# sd-card.net
KiCad netlist of a schematic drawn in Altium Designer
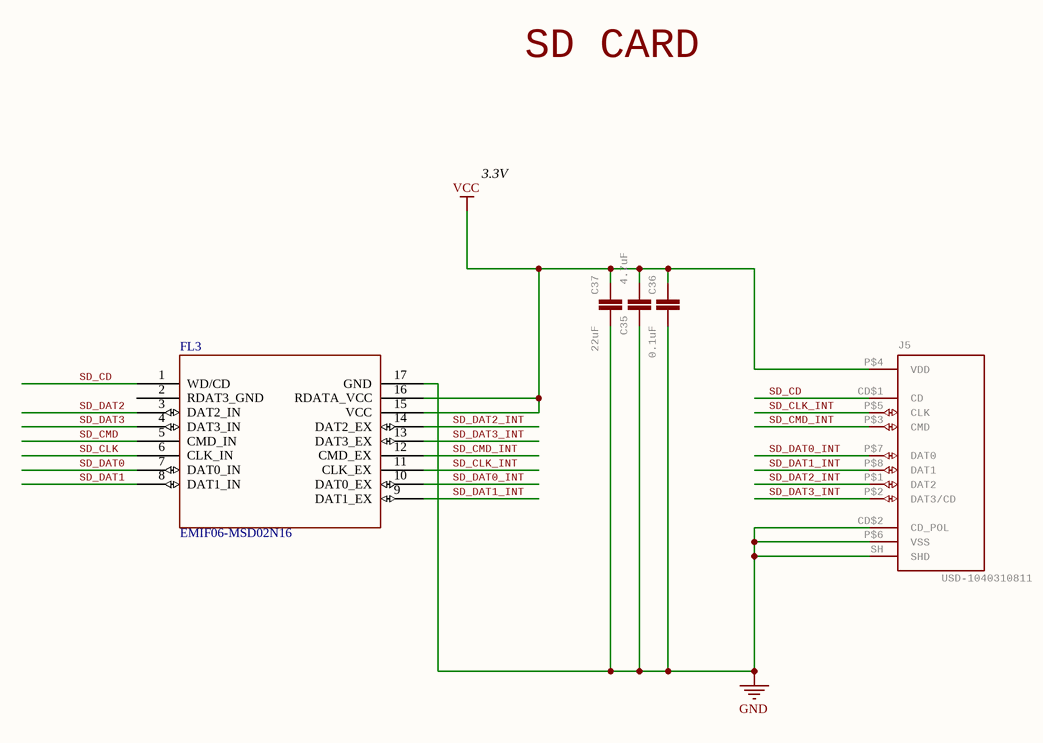
[diagram p0: sd-card.SchDoc]

(export (version "E")
  (design (tool "Eeschema 10.0.6"))
  (components
    (comp (ref "C35")
      (value "4.7uF")
      (footprint "0402-CAP")
      (description "CapacitorStandard 0603 ceramic capacitor, and 0.1\" leaded capacitor.")
      (fields (field (name "MPN") "JMK105BBJ475MV-F"))
      (libsource (lib "rt10") (part "CAP0402-CAP"))
    )
    (comp (ref "C36")
      (value "0.1uF")
      (footprint "0402-CAP")
      (description "CAPACITOR, European symbol")
      (fields (field (name "MPN") "C0402C104Z4VAC"))
      (libsource (lib "rt10") (part "C-EUC0201"))
    )
    (comp (ref "C37")
      (value "22uF")
      (footprint "0805")
      (fields (field (name "MPN") "CL21A226MQQNNNE"))
      (libsource (lib "rt10") (part "22UF-0805-6.3V-20%"))
    )
    (comp (ref "FL3")
      (value "EMIF06-MSD02N16")
      (footprint "MICROQFN16_1p25x3p55x0p4_STM")
      (description "No Description Available")
      (libsource (lib "rt10") (part "EMIF06-MSD02N16"))
    )
    (comp (ref "J5")
      (value "USD-1040310811")
      (footprint "1040310811")
      (description "uSD Slot")
      (fields (field (name "MPN") "104031-0811"))
      (libsource (lib "rt10") (part "USD-1040310811"))
    )
  )
  (nets
    (net (code "1") (name "/SD_CD") (class "Default")
      (node (ref "FL3") (pin "1") (pinfunction "WD/CD_1") (pintype "passive"))
      (node (ref "J5") (pin "CD$1") (pinfunction "CD_CD$1") (pintype "power_in"))
    )
    (net (code "2") (name "/SD_CLK") (class "Default")
      (node (ref "FL3") (pin "6") (pinfunction "CLK_IN_6") (pintype "passive"))
    )
    (net (code "3") (name "/SD_CLK_INT") (class "Default")
      (node (ref "FL3") (pin "11") (pinfunction "CLK_EX_11") (pintype "passive"))
      (node (ref "J5") (pin "P$5") (pinfunction "CLK_P$5") (pintype "bidirectional"))
    )
    (net (code "4") (name "/SD_CMD") (class "Default")
      (node (ref "FL3") (pin "5") (pinfunction "CMD_IN_5") (pintype "passive"))
    )
    (net (code "5") (name "/SD_CMD_INT") (class "Default")
      (node (ref "FL3") (pin "12") (pinfunction "CMD_EX_12") (pintype "passive"))
      (node (ref "J5") (pin "P$3") (pinfunction "CMD_P$3") (pintype "bidirectional"))
    )
    (net (code "6") (name "/SD_DAT0") (class "Default")
      (node (ref "FL3") (pin "7") (pinfunction "DAT0_IN_7") (pintype "bidirectional"))
    )
    (net (code "7") (name "/SD_DAT0_INT") (class "Default")
      (node (ref "FL3") (pin "10") (pinfunction "DAT0_EX_10") (pintype "bidirectional"))
      (node (ref "J5") (pin "P$7") (pinfunction "DAT0_P$7") (pintype "bidirectional"))
    )
    (net (code "8") (name "/SD_DAT1") (class "Default")
      (node (ref "FL3") (pin "8") (pinfunction "DAT1_IN_8") (pintype "bidirectional"))
    )
    (net (code "9") (name "/SD_DAT1_INT") (class "Default")
      (node (ref "FL3") (pin "9") (pinfunction "DAT1_EX_9") (pintype "bidirectional"))
      (node (ref "J5") (pin "P$8") (pinfunction "DAT1_P$8") (pintype "bidirectional"))
    )
    (net (code "10") (name "/SD_DAT2") (class "Default")
      (node (ref "FL3") (pin "3") (pinfunction "DAT2_IN_3") (pintype "bidirectional"))
    )
    (net (code "11") (name "/SD_DAT2_INT") (class "Default")
      (node (ref "FL3") (pin "14") (pinfunction "DAT2_EX_14") (pintype "bidirectional"))
      (node (ref "J5") (pin "P$1") (pinfunction "DAT2_P$1") (pintype "bidirectional"))
    )
    (net (code "12") (name "/SD_DAT3") (class "Default")
      (node (ref "FL3") (pin "4") (pinfunction "DAT3_IN_4") (pintype "bidirectional"))
    )
    (net (code "13") (name "/SD_DAT3_INT") (class "Default")
      (node (ref "FL3") (pin "13") (pinfunction "DAT3_EX_13") (pintype "bidirectional"))
      (node (ref "J5") (pin "P$2") (pinfunction "DAT3/CD_P$2") (pintype "bidirectional"))
    )
    (net (code "14") (name "GND") (class "Default")
      (node (ref "C35") (pin "1") (pinfunction "1_1") (pintype "passive"))
      (node (ref "C36") (pin "2") (pinfunction "2_2") (pintype "passive"))
      (node (ref "C37") (pin "2") (pinfunction "2_2") (pintype "passive"))
      (node (ref "FL3") (pin "17") (pinfunction "GND_17") (pintype "power_in"))
      (node (ref "J5") (pin "CD$2") (pinfunction "CD_POL_CD$2") (pintype "power_in"))
      (node (ref "J5") (pin "P$6") (pinfunction "VSS_P$6") (pintype "power_in"))
      (node (ref "J5") (pin "SH") (pinfunction "SHD_SH") (pintype "power_in"))
    )
    (net (code "15") (name "VCC") (class "Default")
      (node (ref "C35") (pin "2") (pinfunction "2_2") (pintype "passive"))
      (node (ref "C36") (pin "1") (pinfunction "1_1") (pintype "passive"))
      (node (ref "C37") (pin "1") (pinfunction "1_1") (pintype "passive"))
      (node (ref "FL3") (pin "15") (pinfunction "VCC_15") (pintype "power_in"))
      (node (ref "FL3") (pin "16") (pinfunction "RDATA_VCC_16") (pintype "passive"))
      (node (ref "J5") (pin "P$4") (pinfunction "VDD_P$4") (pintype "power_in"))
    )
    (net (code "16") (name "unconnected-(FL3-RDAT3_GND-Pad2)") (class "Default")
      (node (ref "FL3") (pin "2") (pinfunction "RDAT3_GND_2") (pintype "power_in"))
    )
  )
)
